# Level-Shifter-4_v11.net
KiCad netlist of a schematic drawn in EAGLE
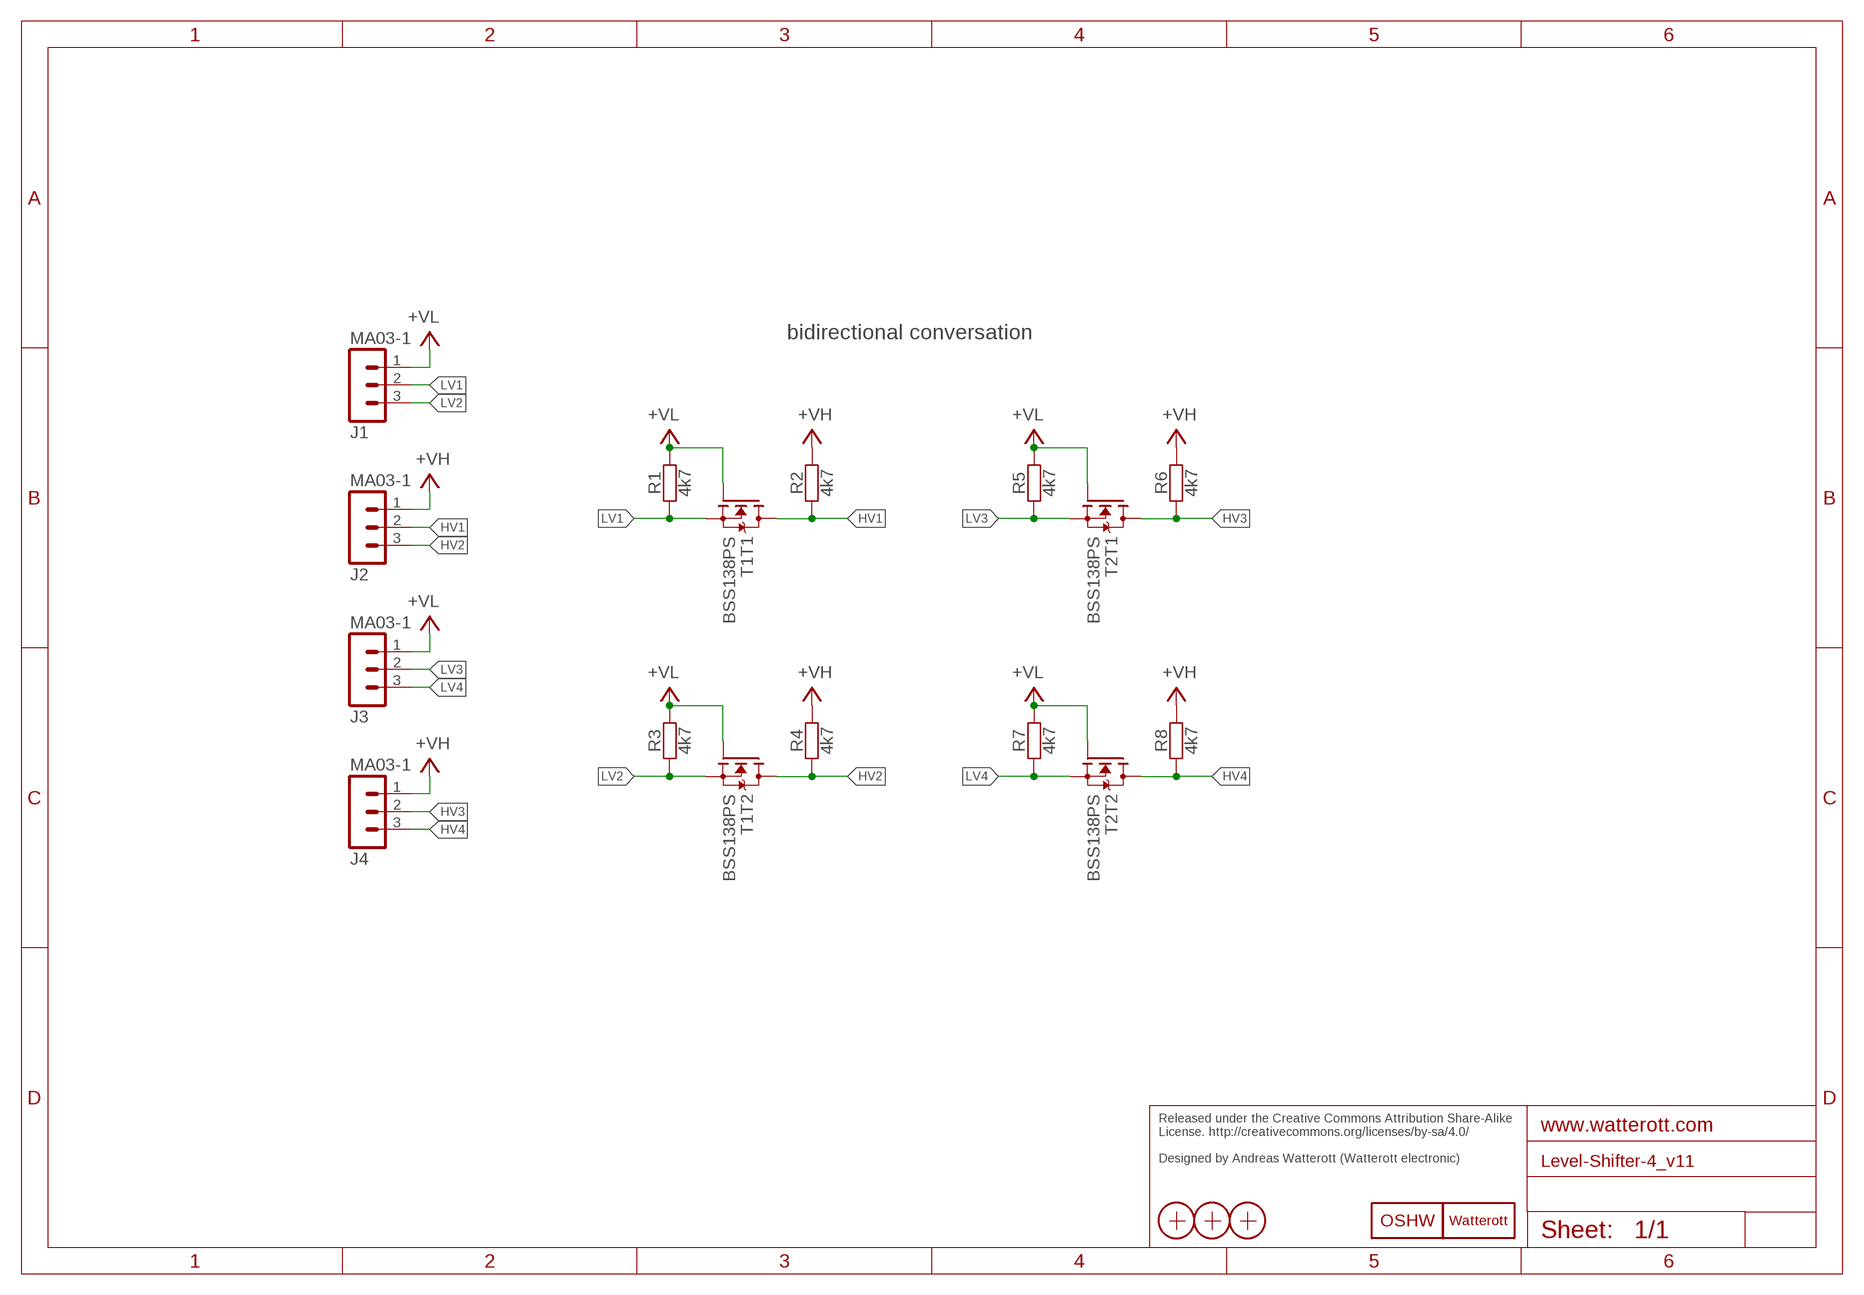
[diagram p0: schematic, sheet 1]

(export (version "E")
  (design (tool "Eeschema 10.0.6"))
  (components
    (comp (ref "J1")
      (value "MA03-1")
      (footprint "eagle-import:MA03-1")
      (libsource (lib "eagle-import") (part "MA03-1"))
    )
    (comp (ref "J2")
      (value "MA03-1")
      (footprint "eagle-import:MA03-1")
      (libsource (lib "eagle-import") (part "MA03-1"))
    )
    (comp (ref "J3")
      (value "MA03-1")
      (footprint "eagle-import:MA03-1")
      (libsource (lib "eagle-import") (part "MA03-1"))
    )
    (comp (ref "J4")
      (value "MA03-1")
      (footprint "eagle-import:MA03-1")
      (libsource (lib "eagle-import") (part "MA03-1"))
    )
    (comp (ref "LOGO1")
      (value "OSHW_LOGOX0070")
      (footprint "eagle-import:OSHW_6X70")
      (libsource (lib "eagle-import") (part "OSHW_LOGOX0070"))
    )
    (comp (ref "LOGO2")
      (value "LOGO-S_PLACE_S")
      (footprint "eagle-import:SPARK_TPLACE_S")
      (libsource (lib "eagle-import") (part "LOGO-S_PLACE_S"))
    )
    (comp (ref "R1")
      (value "4k7")
      (footprint "eagle-import:C0402")
      (libsource (lib "eagle-import") (part "RESISTOR-0402"))
    )
    (comp (ref "R2")
      (value "4k7")
      (footprint "eagle-import:C0402")
      (libsource (lib "eagle-import") (part "RESISTOR-0402"))
    )
    (comp (ref "R3")
      (value "4k7")
      (footprint "eagle-import:C0402")
      (libsource (lib "eagle-import") (part "RESISTOR-0402"))
    )
    (comp (ref "R4")
      (value "4k7")
      (footprint "eagle-import:C0402")
      (libsource (lib "eagle-import") (part "RESISTOR-0402"))
    )
    (comp (ref "R5")
      (value "4k7")
      (footprint "eagle-import:C0402")
      (libsource (lib "eagle-import") (part "RESISTOR-0402"))
    )
    (comp (ref "R6")
      (value "4k7")
      (footprint "eagle-import:C0402")
      (libsource (lib "eagle-import") (part "RESISTOR-0402"))
    )
    (comp (ref "R7")
      (value "4k7")
      (footprint "eagle-import:C0402")
      (libsource (lib "eagle-import") (part "RESISTOR-0402"))
    )
    (comp (ref "R8")
      (value "4k7")
      (footprint "eagle-import:C0402")
      (libsource (lib "eagle-import") (part "RESISTOR-0402"))
    )
    (comp (ref "T1")
      (value "BSS138PS")
      (footprint "eagle-import:SOT363")
      (libsource (lib "eagle-import") (part "BSS138PS"))
    )
    (comp (ref "T2")
      (value "BSS138PS")
      (footprint "eagle-import:SOT363")
      (libsource (lib "eagle-import") (part "BSS138PS"))
    )
    (comp (ref "X1")
      (value "PASSER-07")
      (footprint "eagle-import:PASSER_07MM")
      (libsource (lib "eagle-import") (part "PASSER-07"))
    )
    (comp (ref "X2")
      (value "PASSER-07")
      (footprint "eagle-import:PASSER_07MM")
      (libsource (lib "eagle-import") (part "PASSER-07"))
    )
    (comp (ref "X3")
      (value "PASSER-07")
      (footprint "eagle-import:PASSER_07MM")
      (libsource (lib "eagle-import") (part "PASSER-07"))
    )
  )
  (nets
    (net (code "1") (name "+VH") (class "Default")
      (node (ref "J2") (pin "1") (pinfunction "1_1") (pintype "passive"))
      (node (ref "J4") (pin "1") (pinfunction "1_1") (pintype "passive"))
      (node (ref "R2") (pin "2") (pinfunction "2_2") (pintype "passive"))
      (node (ref "R4") (pin "2") (pinfunction "2_2") (pintype "passive"))
      (node (ref "R6") (pin "2") (pinfunction "2_2") (pintype "passive"))
      (node (ref "R8") (pin "2") (pinfunction "2_2") (pintype "passive"))
    )
    (net (code "2") (name "+VL") (class "Default")
      (node (ref "J1") (pin "1") (pinfunction "1_1") (pintype "passive"))
      (node (ref "J3") (pin "1") (pinfunction "1_1") (pintype "passive"))
      (node (ref "R1") (pin "2") (pinfunction "2_2") (pintype "passive"))
      (node (ref "R3") (pin "2") (pinfunction "2_2") (pintype "passive"))
      (node (ref "R5") (pin "2") (pinfunction "2_2") (pintype "passive"))
      (node (ref "R7") (pin "2") (pinfunction "2_2") (pintype "passive"))
      (node (ref "T1") (pin "2") (pinfunction "G_2") (pintype "passive"))
      (node (ref "T1") (pin "5") (pinfunction "G_5") (pintype "passive"))
      (node (ref "T2") (pin "2") (pinfunction "G_2") (pintype "passive"))
      (node (ref "T2") (pin "5") (pinfunction "G_5") (pintype "passive"))
    )
    (net (code "3") (name "HV1") (class "Default")
      (node (ref "J2") (pin "2") (pinfunction "2_2") (pintype "passive"))
      (node (ref "R2") (pin "1") (pinfunction "1_1") (pintype "passive"))
      (node (ref "T1") (pin "6") (pinfunction "D_6") (pintype "passive"))
    )
    (net (code "4") (name "HV2") (class "Default")
      (node (ref "J2") (pin "3") (pinfunction "3_3") (pintype "passive"))
      (node (ref "R4") (pin "1") (pinfunction "1_1") (pintype "passive"))
      (node (ref "T1") (pin "3") (pinfunction "D_3") (pintype "passive"))
    )
    (net (code "5") (name "HV3") (class "Default")
      (node (ref "J4") (pin "2") (pinfunction "2_2") (pintype "passive"))
      (node (ref "R6") (pin "1") (pinfunction "1_1") (pintype "passive"))
      (node (ref "T2") (pin "6") (pinfunction "D_6") (pintype "passive"))
    )
    (net (code "6") (name "HV4") (class "Default")
      (node (ref "J4") (pin "3") (pinfunction "3_3") (pintype "passive"))
      (node (ref "R8") (pin "1") (pinfunction "1_1") (pintype "passive"))
      (node (ref "T2") (pin "3") (pinfunction "D_3") (pintype "passive"))
    )
    (net (code "7") (name "LV1") (class "Default")
      (node (ref "J1") (pin "2") (pinfunction "2_2") (pintype "passive"))
      (node (ref "R1") (pin "1") (pinfunction "1_1") (pintype "passive"))
      (node (ref "T1") (pin "1") (pinfunction "S_1") (pintype "passive"))
    )
    (net (code "8") (name "LV2") (class "Default")
      (node (ref "J1") (pin "3") (pinfunction "3_3") (pintype "passive"))
      (node (ref "R3") (pin "1") (pinfunction "1_1") (pintype "passive"))
      (node (ref "T1") (pin "4") (pinfunction "S_4") (pintype "passive"))
    )
    (net (code "9") (name "LV3") (class "Default")
      (node (ref "J3") (pin "2") (pinfunction "2_2") (pintype "passive"))
      (node (ref "R5") (pin "1") (pinfunction "1_1") (pintype "passive"))
      (node (ref "T2") (pin "1") (pinfunction "S_1") (pintype "passive"))
    )
    (net (code "10") (name "LV4") (class "Default")
      (node (ref "J3") (pin "3") (pinfunction "3_3") (pintype "passive"))
      (node (ref "R7") (pin "1") (pinfunction "1_1") (pintype "passive"))
      (node (ref "T2") (pin "4") (pinfunction "S_4") (pintype "passive"))
    )
  )
)
